# sensor.net
KiCad netlist of a schematic drawn in Altium Designer
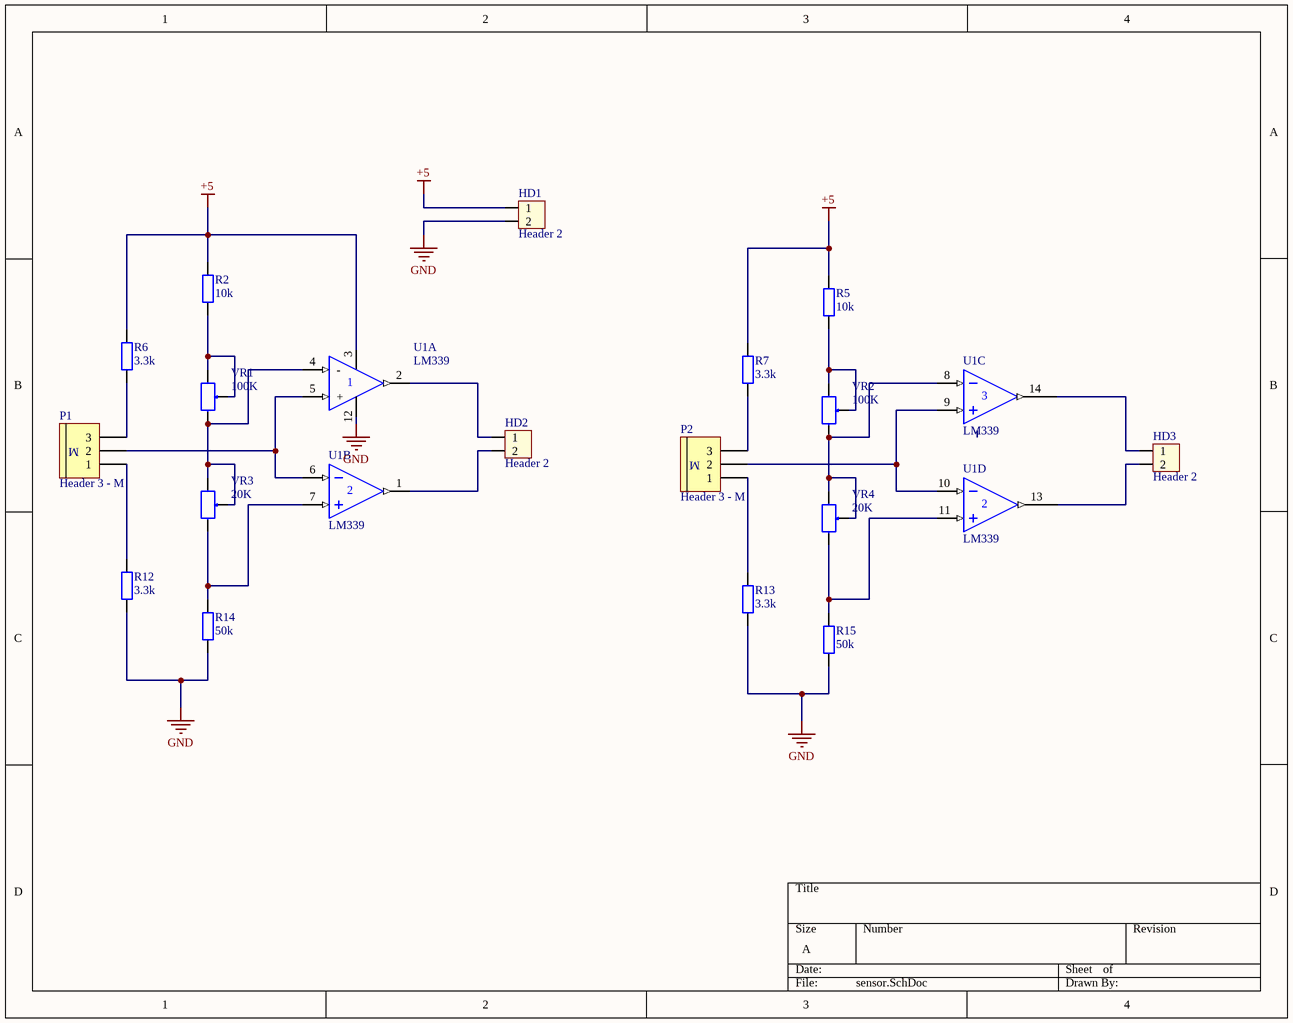
[diagram p0: sensor.SchDoc]

(export (version "E")
  (design (tool "Eeschema 10.0.6"))
  (components
    (comp (ref "HD1")
      (value "Header 2")
      (footprint "HED2")
      (description "Header 2 (Green)")
      (libsource (lib "My Library") (part "Hed2"))
    )
    (comp (ref "HD2")
      (value "Header 2")
      (footprint "HED2")
      (description "Header 2 (Green)")
      (libsource (lib "My Library") (part "Hed2"))
    )
    (comp (ref "HD3")
      (value "Header 2")
      (footprint "HED2")
      (description "Header 2 (Green)")
      (libsource (lib "My Library") (part "Hed2"))
    )
    (comp (ref "P1")
      (value "Header 3 - M")
      (footprint "Medium - Header 3")
      (description "Header, 3-Pin, Medium")
      (fields (field (name "PUBLISHER") "Altium Limited"))
      (libsource (lib "My Library") (part "Header 3 - M"))
    )
    (comp (ref "P2")
      (value "Header 3 - M")
      (footprint "Medium - Header 3")
      (description "Header, 3-Pin, Medium")
      (fields (field (name "PUBLISHER") "Altium Limited"))
      (libsource (lib "My Library") (part "Header 3 - M"))
    )
    (comp (ref "R2")
      (value "10k")
      (footprint "R1/4W")
      (description "Resistor 1/4W")
      (libsource (lib "syhaunguyen") (part "R1/4W"))
    )
    (comp (ref "R5")
      (value "10k")
      (footprint "R1/4W")
      (description "Resistor 1/4W")
      (libsource (lib "syhaunguyen") (part "R1/4W"))
    )
    (comp (ref "R6")
      (value "3.3k")
      (footprint "R1/4W")
      (description "Resistor 1/4W")
      (libsource (lib "syhaunguyen") (part "R1/4W"))
    )
    (comp (ref "R7")
      (value "3.3k")
      (footprint "R1/4W")
      (description "Resistor 1/4W")
      (libsource (lib "syhaunguyen") (part "R1/4W"))
    )
    (comp (ref "R12")
      (value "3.3k")
      (footprint "R1/4W")
      (description "Resistor 1/4W")
      (libsource (lib "syhaunguyen") (part "R1/4W"))
    )
    (comp (ref "R13")
      (value "3.3k")
      (footprint "R1/4W")
      (description "Resistor 1/4W")
      (libsource (lib "syhaunguyen") (part "R1/4W"))
    )
    (comp (ref "R14")
      (value "50k")
      (footprint "R1/4W")
      (description "Resistor 1/4W")
      (libsource (lib "syhaunguyen") (part "R1/4W"))
    )
    (comp (ref "R15")
      (value "50k")
      (footprint "R1/4W")
      (description "Resistor 1/4W")
      (libsource (lib "syhaunguyen") (part "R1/4W"))
    )
    (comp (ref "U1")
      (value "LM339")
      (footprint "DIP14")
      (description "Low Power Low Offset Voltage Quad Comparators")
      (libsource (lib "My Library") (part "LM339"))
    )
    (comp (ref "VR1")
      (value "100K")
      (footprint "VR")
      (description "Var Resistor")
      (libsource (lib "My Library") (part "VR"))
    )
    (comp (ref "VR2")
      (value "100K")
      (footprint "VR")
      (description "Var Resistor")
      (libsource (lib "My Library") (part "VR"))
    )
    (comp (ref "VR3")
      (value "20K")
      (footprint "VR")
      (description "Var Resistor")
      (libsource (lib "My Library") (part "VR"))
    )
    (comp (ref "VR4")
      (value "20K")
      (footprint "VR")
      (description "Var Resistor")
      (libsource (lib "My Library") (part "VR"))
    )
  )
  (nets
    (net (code "1") (name "+5") (class "Default")
      (node (ref "HD1") (pin "1") (pinfunction "1_1") (pintype "passive"))
      (node (ref "R2") (pin "2") (pinfunction "2_2") (pintype "passive"))
      (node (ref "R5") (pin "2") (pinfunction "2_2") (pintype "passive"))
      (node (ref "R6") (pin "2") (pinfunction "2_2") (pintype "passive"))
      (node (ref "R7") (pin "2") (pinfunction "2_2") (pintype "passive"))
      (node (ref "U1") (pin "3") (pinfunction "VCC_3") (pintype "power_in"))
    )
    (net (code "2") (name "GND") (class "Default")
      (node (ref "HD1") (pin "2") (pinfunction "2_2") (pintype "passive"))
      (node (ref "R12") (pin "1") (pinfunction "1_1") (pintype "passive"))
      (node (ref "R13") (pin "1") (pinfunction "1_1") (pintype "passive"))
      (node (ref "R14") (pin "1") (pinfunction "1_1") (pintype "passive"))
      (node (ref "R15") (pin "1") (pinfunction "1_1") (pintype "passive"))
      (node (ref "U1") (pin "12") (pinfunction "GND_12") (pintype "power_in"))
    )
    (net (code "3") (name "Net-(P1-Pad1)") (class "Default")
      (node (ref "P1") (pin "1") (pinfunction "1_1") (pintype "passive"))
      (node (ref "R12") (pin "2") (pinfunction "2_2") (pintype "passive"))
    )
    (net (code "4") (name "Net-(P1-Pad3)") (class "Default")
      (node (ref "P1") (pin "3") (pinfunction "3_3") (pintype "passive"))
      (node (ref "R6") (pin "1") (pinfunction "1_1") (pintype "passive"))
    )
    (net (code "5") (name "Net-(P2-Pad1)") (class "Default")
      (node (ref "P2") (pin "1") (pinfunction "1_1") (pintype "passive"))
      (node (ref "R13") (pin "2") (pinfunction "2_2") (pintype "passive"))
    )
    (net (code "6") (name "Net-(P2-Pad3)") (class "Default")
      (node (ref "P2") (pin "3") (pinfunction "3_3") (pintype "passive"))
      (node (ref "R7") (pin "1") (pinfunction "1_1") (pintype "passive"))
    )
    (net (code "7") (name "Net-(R2-Pad1)") (class "Default")
      (node (ref "R2") (pin "1") (pinfunction "1_1") (pintype "passive"))
      (node (ref "VR1") (pin "1") (pinfunction "1_1") (pintype "passive"))
      (node (ref "VR1") (pin "2") (pinfunction "2_2") (pintype "passive"))
    )
    (net (code "8") (name "Net-(R5-Pad1)") (class "Default")
      (node (ref "R5") (pin "1") (pinfunction "1_1") (pintype "passive"))
      (node (ref "VR2") (pin "1") (pinfunction "1_1") (pintype "passive"))
      (node (ref "VR2") (pin "2") (pinfunction "2_2") (pintype "passive"))
    )
    (net (code "9") (name "Net-(U1A-+)") (class "Default")
      (node (ref "P1") (pin "2") (pinfunction "2_2") (pintype "passive"))
      (node (ref "U1") (pin "5") (pinfunction "+_5") (pintype "input"))
      (node (ref "U1") (pin "6") (pinfunction "IN-_6") (pintype "input"))
    )
    (net (code "10") (name "Net-(U1A--)") (class "Default")
      (node (ref "U1") (pin "4") (pinfunction "-_4") (pintype "input"))
      (node (ref "VR1") (pin "3") (pinfunction "3_3") (pintype "passive"))
      (node (ref "VR3") (pin "1") (pinfunction "1_1") (pintype "passive"))
      (node (ref "VR3") (pin "2") (pinfunction "2_2") (pintype "passive"))
    )
    (net (code "11") (name "Net-(U1A-OUT)") (class "Default")
      (node (ref "HD2") (pin "1") (pinfunction "1_1") (pintype "passive"))
      (node (ref "U1") (pin "2") (pinfunction "OUT_2") (pintype "output"))
    )
    (net (code "12") (name "Net-(U1B-IN+)") (class "Default")
      (node (ref "R14") (pin "2") (pinfunction "2_2") (pintype "passive"))
      (node (ref "U1") (pin "7") (pinfunction "IN+_7") (pintype "input"))
      (node (ref "VR3") (pin "3") (pinfunction "3_3") (pintype "passive"))
    )
    (net (code "13") (name "Net-(U1B-OUT)") (class "Default")
      (node (ref "HD2") (pin "2") (pinfunction "2_2") (pintype "passive"))
      (node (ref "U1") (pin "1") (pinfunction "OUT_1") (pintype "output"))
    )
    (net (code "14") (name "Net-(U1C-15)") (class "Default")
      (node (ref "HD3") (pin "1") (pinfunction "1_1") (pintype "passive"))
      (node (ref "U1") (pin "14") (pinfunction "15_14") (pintype "output"))
    )
    (net (code "15") (name "Net-(U1C-IN-)") (class "Default")
      (node (ref "P2") (pin "2") (pinfunction "2_2") (pintype "passive"))
      (node (ref "U1") (pin "10") (pinfunction "IN-_10") (pintype "input"))
      (node (ref "U1") (pin "9") (pinfunction "IN-_9") (pintype "input"))
    )
    (net (code "16") (name "Net-(U1C-OUT)") (class "Default")
      (node (ref "U1") (pin "8") (pinfunction "OUT_8") (pintype "input"))
      (node (ref "VR2") (pin "3") (pinfunction "3_3") (pintype "passive"))
      (node (ref "VR4") (pin "1") (pinfunction "1_1") (pintype "passive"))
      (node (ref "VR4") (pin "2") (pinfunction "2_2") (pintype "passive"))
    )
    (net (code "17") (name "Net-(U1D-15)") (class "Default")
      (node (ref "HD3") (pin "2") (pinfunction "2_2") (pintype "passive"))
      (node (ref "U1") (pin "13") (pinfunction "15_13") (pintype "output"))
    )
    (net (code "18") (name "Net-(U1D-IN+)") (class "Default")
      (node (ref "R15") (pin "2") (pinfunction "2_2") (pintype "passive"))
      (node (ref "U1") (pin "11") (pinfunction "IN+_11") (pintype "input"))
      (node (ref "VR4") (pin "3") (pinfunction "3_3") (pintype "passive"))
    )
  )
)
